# Clipcord_BOT.net
KiCad netlist of a schematic drawn in EAGLE
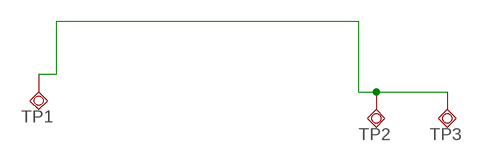
[diagram p0: schematic, sheet 1]

(export (version "E")
  (design (tool "Eeschema 10.0.6"))
  (components
    (comp (ref "TP1")
      (value "TESTPAD_TPSQB1,27")
      (footprint "eagle-import:TESTPAD_B1,27")
      (libsource (lib "eagle-import") (part "TESTPAD_TPSQB1,27"))
    )
    (comp (ref "TP2")
      (value "TESTPAD_TPSQB1,27")
      (footprint "eagle-import:TESTPAD_B1,27")
      (libsource (lib "eagle-import") (part "TESTPAD_TPSQB1,27"))
    )
    (comp (ref "TP3")
      (value "TESTPAD_TPSQB1,27")
      (footprint "eagle-import:TESTPAD_B1,27")
      (libsource (lib "eagle-import") (part "TESTPAD_TPSQB1,27"))
    )
  )
  (nets
    (net (code "1") (name "Net-(TP1-PadTP)") (class "Default")
      (node (ref "TP1") (pin "TP") (pinfunction "TP_TP") (pintype "input"))
      (node (ref "TP2") (pin "TP") (pinfunction "TP_TP") (pintype "input"))
      (node (ref "TP3") (pin "TP") (pinfunction "TP_TP") (pintype "input"))
    )
  )
)
